# tophat.net
KiCad netlist of a schematic drawn in EAGLE
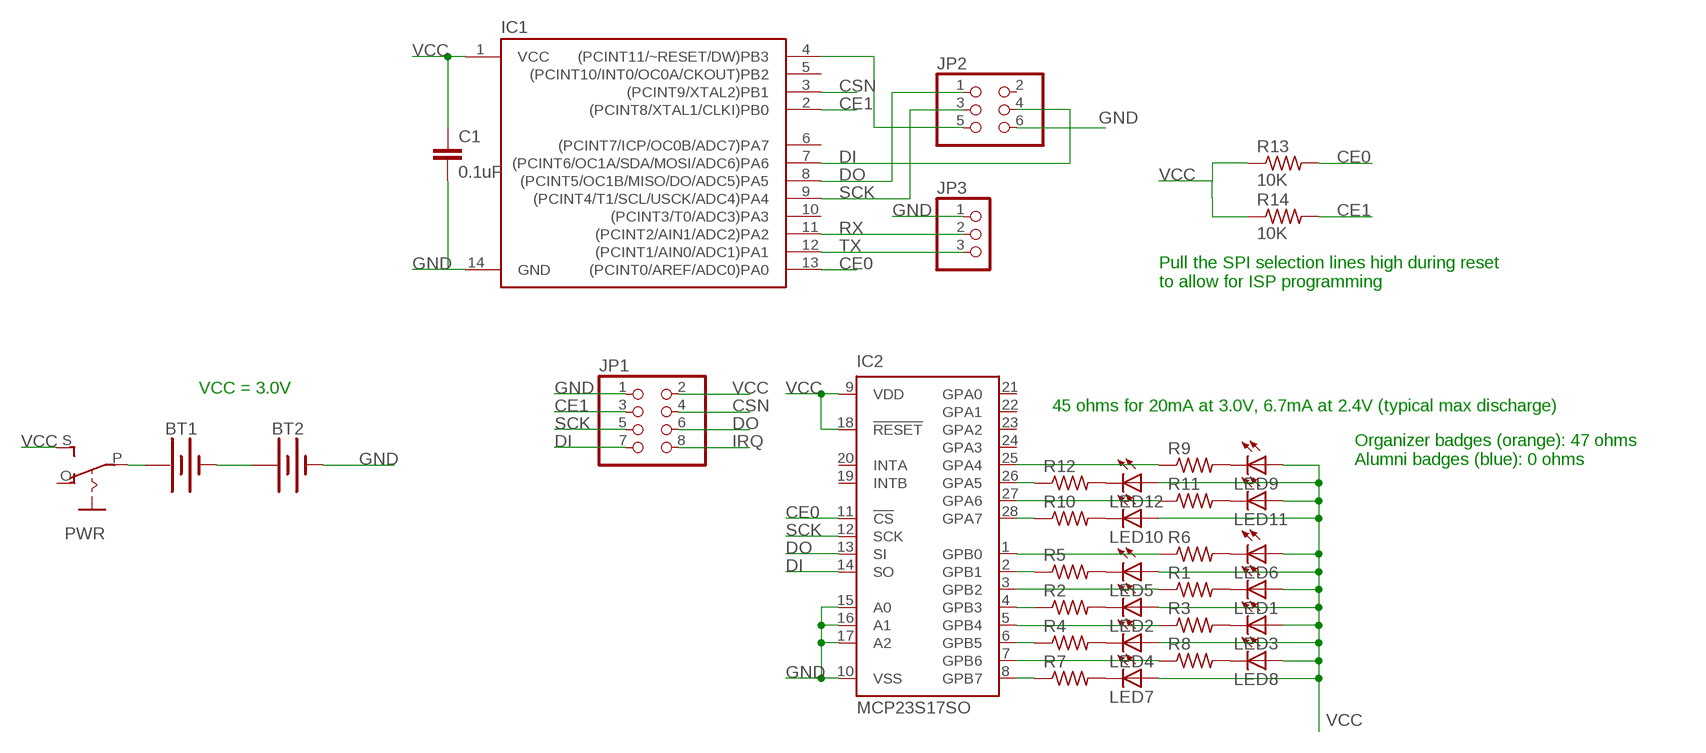
[diagram p0: schematic, sheet 1]

(export (version "E")
  (design (tool "Eeschema 10.0.6"))
  (components
    (comp (ref "BT1")
      (value "BATTERY-AA-SMD")
      (footprint "eagle-import:BATTERY-AA-SMD")
      (libsource (lib "eagle-import") (part "BATTERY-AA-SMD"))
    )
    (comp (ref "BT2")
      (value "BATTERY-AA-SMD")
      (footprint "eagle-import:BATTERY-AA-SMD")
      (libsource (lib "eagle-import") (part "BATTERY-AA-SMD"))
    )
    (comp (ref "C1")
      (value "0.1uF")
      (footprint "eagle-import:C1206")
      (libsource (lib "eagle-import") (part "C-EUC1206"))
    )
    (comp (ref "IC1")
      (value "ATTINY84")
      (footprint "eagle-import:SO14")
      (libsource (lib "eagle-import") (part "ATTINY84"))
    )
    (comp (ref "IC2")
      (value "MCP23S17SO")
      (footprint "eagle-import:SO28W")
      (fields (field (name "MF") "MICROCHIP") (field (name "MPN") "MCP23S17-E/SO"))
      (libsource (lib "eagle-import") (part "MCP23S17SO"))
    )
    (comp (ref "JP1")
      (value "PINHD-2X4/90")
      (footprint "eagle-import:2X04_90")
      (libsource (lib "eagle-import") (part "PINHD-2X4/90"))
    )
    (comp (ref "JP2")
      (value "PINHD-2X3")
      (footprint "eagle-import:2X03")
      (libsource (lib "eagle-import") (part "PINHD-2X3"))
    )
    (comp (ref "JP3")
      (value "PINHD-1X3")
      (footprint "eagle-import:1X03")
      (libsource (lib "eagle-import") (part "PINHD-1X3"))
    )
    (comp (ref "LED1")
      (value "LEDSMT1206")
      (footprint "eagle-import:1206")
      (libsource (lib "eagle-import") (part "LEDSMT1206"))
    )
    (comp (ref "LED2")
      (value "LEDSMT1206")
      (footprint "eagle-import:1206")
      (libsource (lib "eagle-import") (part "LEDSMT1206"))
    )
    (comp (ref "LED3")
      (value "LEDSMT1206")
      (footprint "eagle-import:1206")
      (libsource (lib "eagle-import") (part "LEDSMT1206"))
    )
    (comp (ref "LED4")
      (value "LEDSMT1206")
      (footprint "eagle-import:1206")
      (libsource (lib "eagle-import") (part "LEDSMT1206"))
    )
    (comp (ref "LED5")
      (value "LEDSMT1206")
      (footprint "eagle-import:1206")
      (libsource (lib "eagle-import") (part "LEDSMT1206"))
    )
    (comp (ref "LED6")
      (value "LEDSMT1206")
      (footprint "eagle-import:1206")
      (libsource (lib "eagle-import") (part "LEDSMT1206"))
    )
    (comp (ref "LED7")
      (value "LEDSMT1206")
      (footprint "eagle-import:1206")
      (libsource (lib "eagle-import") (part "LEDSMT1206"))
    )
    (comp (ref "LED8")
      (value "LEDSMT1206")
      (footprint "eagle-import:1206")
      (libsource (lib "eagle-import") (part "LEDSMT1206"))
    )
    (comp (ref "LED9")
      (value "LEDSMT1206")
      (footprint "eagle-import:1206")
      (libsource (lib "eagle-import") (part "LEDSMT1206"))
    )
    (comp (ref "LED10")
      (value "LEDSMT1206")
      (footprint "eagle-import:1206")
      (libsource (lib "eagle-import") (part "LEDSMT1206"))
    )
    (comp (ref "LED11")
      (value "LEDSMT1206")
      (footprint "eagle-import:1206")
      (libsource (lib "eagle-import") (part "LEDSMT1206"))
    )
    (comp (ref "LED12")
      (value "LEDSMT1206")
      (footprint "eagle-import:1206")
      (libsource (lib "eagle-import") (part "LEDSMT1206"))
    )
    (comp (ref "PWR")
      (value "EG1218S")
      (footprint "eagle-import:EG1218")
      (libsource (lib "eagle-import") (part "EG1218S"))
    )
    (comp (ref "R1")
      (value "R-US_R1206")
      (footprint "eagle-import:R1206")
      (libsource (lib "eagle-import") (part "R-US_R1206"))
    )
    (comp (ref "R2")
      (value "R-US_R1206")
      (footprint "eagle-import:R1206")
      (libsource (lib "eagle-import") (part "R-US_R1206"))
    )
    (comp (ref "R3")
      (value "R-US_R1206")
      (footprint "eagle-import:R1206")
      (libsource (lib "eagle-import") (part "R-US_R1206"))
    )
    (comp (ref "R4")
      (value "R-US_R1206")
      (footprint "eagle-import:R1206")
      (libsource (lib "eagle-import") (part "R-US_R1206"))
    )
    (comp (ref "R5")
      (value "R-US_R1206")
      (footprint "eagle-import:R1206")
      (libsource (lib "eagle-import") (part "R-US_R1206"))
    )
    (comp (ref "R6")
      (value "R-US_R1206")
      (footprint "eagle-import:R1206")
      (libsource (lib "eagle-import") (part "R-US_R1206"))
    )
    (comp (ref "R7")
      (value "R-US_R1206")
      (footprint "eagle-import:R1206")
      (libsource (lib "eagle-import") (part "R-US_R1206"))
    )
    (comp (ref "R8")
      (value "R-US_R1206")
      (footprint "eagle-import:R1206")
      (libsource (lib "eagle-import") (part "R-US_R1206"))
    )
    (comp (ref "R9")
      (value "R-US_R1206")
      (footprint "eagle-import:R1206")
      (libsource (lib "eagle-import") (part "R-US_R1206"))
    )
    (comp (ref "R10")
      (value "R-US_R1206")
      (footprint "eagle-import:R1206")
      (libsource (lib "eagle-import") (part "R-US_R1206"))
    )
    (comp (ref "R11")
      (value "R-US_R1206")
      (footprint "eagle-import:R1206")
      (libsource (lib "eagle-import") (part "R-US_R1206"))
    )
    (comp (ref "R12")
      (value "R-US_R1206")
      (footprint "eagle-import:R1206")
      (libsource (lib "eagle-import") (part "R-US_R1206"))
    )
    (comp (ref "R13")
      (value "10K")
      (footprint "eagle-import:R1206")
      (libsource (lib "eagle-import") (part "R-US_R1206"))
    )
    (comp (ref "R14")
      (value "10K")
      (footprint "eagle-import:R1206")
      (libsource (lib "eagle-import") (part "R-US_R1206"))
    )
  )
  (nets
    (net (code "1") (name "/CE0") (class "Default")
      (node (ref "IC1") (pin "13") (pinfunction "(PCINT0/AREF/ADC0)PA0_13") (pintype "bidirectional"))
      (node (ref "IC2") (pin "11") (pinfunction "~{CS}_11") (pintype "input"))
      (node (ref "R13") (pin "2") (pinfunction "2_2") (pintype "passive"))
    )
    (net (code "2") (name "/CE1") (class "Default")
      (node (ref "IC1") (pin "2") (pinfunction "(PCINT8/XTAL1/CLKI)PB0_2") (pintype "bidirectional"))
      (node (ref "JP1") (pin "3") (pinfunction "3_3") (pintype "passive"))
      (node (ref "R14") (pin "2") (pinfunction "2_2") (pintype "passive"))
    )
    (net (code "3") (name "/CSN") (class "Default")
      (node (ref "IC1") (pin "3") (pinfunction "(PCINT9/XTAL2)PB1_3") (pintype "bidirectional"))
      (node (ref "JP1") (pin "4") (pinfunction "4_4") (pintype "passive"))
    )
    (net (code "4") (name "/DI") (class "Default")
      (node (ref "IC1") (pin "7") (pinfunction "(PCINT6/OC1A/SDA/MOSI/ADC6)PA6_7") (pintype "bidirectional"))
      (node (ref "IC2") (pin "14") (pinfunction "SO_14") (pintype "output"))
      (node (ref "JP1") (pin "7") (pinfunction "7_7") (pintype "passive"))
      (node (ref "JP2") (pin "4") (pinfunction "4_4") (pintype "passive"))
    )
    (net (code "5") (name "/DO") (class "Default")
      (node (ref "IC1") (pin "8") (pinfunction "(PCINT5/OC1B/MISO/DO/ADC5)PA5_8") (pintype "bidirectional"))
      (node (ref "IC2") (pin "13") (pinfunction "SI_13") (pintype "input"))
      (node (ref "JP1") (pin "6") (pinfunction "6_6") (pintype "passive"))
      (node (ref "JP2") (pin "1") (pinfunction "1_1") (pintype "passive"))
    )
    (net (code "6") (name "/GND") (class "Default")
      (node (ref "BT2") (pin "P$2") (pinfunction "-_P$2") (pintype "power_in"))
      (node (ref "BT2") (pin "P$4") (pinfunction "-_P$4") (pintype "power_in"))
      (node (ref "C1") (pin "2") (pinfunction "2_2") (pintype "passive"))
      (node (ref "IC1") (pin "14") (pinfunction "GND_14") (pintype "bidirectional"))
      (node (ref "IC2") (pin "10") (pinfunction "VSS_10") (pintype "power_in"))
      (node (ref "IC2") (pin "15") (pinfunction "A0_15") (pintype "input"))
      (node (ref "IC2") (pin "16") (pinfunction "A1_16") (pintype "input"))
      (node (ref "IC2") (pin "17") (pinfunction "A2_17") (pintype "input"))
      (node (ref "JP1") (pin "1") (pinfunction "1_1") (pintype "passive"))
      (node (ref "JP2") (pin "6") (pinfunction "6_6") (pintype "passive"))
      (node (ref "JP3") (pin "1") (pinfunction "1_1") (pintype "passive"))
    )
    (net (code "7") (name "/IRQ") (class "Default")
      (node (ref "JP1") (pin "8") (pinfunction "8_8") (pintype "passive"))
    )
    (net (code "8") (name "/RX") (class "Default")
      (node (ref "IC1") (pin "11") (pinfunction "(PCINT2/AIN1/ADC2)PA2_11") (pintype "bidirectional"))
      (node (ref "JP3") (pin "2") (pinfunction "2_2") (pintype "passive"))
    )
    (net (code "9") (name "/SCK") (class "Default")
      (node (ref "IC1") (pin "9") (pinfunction "(PCINT4/T1/SCL/USCK/ADC4)PA4_9") (pintype "bidirectional"))
      (node (ref "IC2") (pin "12") (pinfunction "SCK_12") (pintype "input"))
      (node (ref "JP1") (pin "5") (pinfunction "5_5") (pintype "passive"))
      (node (ref "JP2") (pin "3") (pinfunction "3_3") (pintype "passive"))
    )
    (net (code "10") (name "/TX") (class "Default")
      (node (ref "IC1") (pin "12") (pinfunction "(PCINT1/AIN0/ADC1)PA1_12") (pintype "bidirectional"))
      (node (ref "JP3") (pin "3") (pinfunction "3_3") (pintype "passive"))
    )
    (net (code "11") (name "/VCC") (class "Default")
      (node (ref "C1") (pin "1") (pinfunction "1_1") (pintype "passive"))
      (node (ref "IC1") (pin "1") (pinfunction "VCC_1") (pintype "bidirectional"))
      (node (ref "IC2") (pin "18") (pinfunction "~{RESET}_18") (pintype "input"))
      (node (ref "IC2") (pin "9") (pinfunction "VDD_9") (pintype "power_in"))
      (node (ref "JP1") (pin "2") (pinfunction "2_2") (pintype "passive"))
      (node (ref "LED1") (pin "A") (pinfunction "A_A") (pintype "passive"))
      (node (ref "LED10") (pin "A") (pinfunction "A_A") (pintype "passive"))
      (node (ref "LED11") (pin "A") (pinfunction "A_A") (pintype "passive"))
      (node (ref "LED12") (pin "A") (pinfunction "A_A") (pintype "passive"))
      (node (ref "LED2") (pin "A") (pinfunction "A_A") (pintype "passive"))
      (node (ref "LED3") (pin "A") (pinfunction "A_A") (pintype "passive"))
      (node (ref "LED4") (pin "A") (pinfunction "A_A") (pintype "passive"))
      (node (ref "LED5") (pin "A") (pinfunction "A_A") (pintype "passive"))
      (node (ref "LED6") (pin "A") (pinfunction "A_A") (pintype "passive"))
      (node (ref "LED7") (pin "A") (pinfunction "A_A") (pintype "passive"))
      (node (ref "LED8") (pin "A") (pinfunction "A_A") (pintype "passive"))
      (node (ref "LED9") (pin "A") (pinfunction "A_A") (pintype "passive"))
      (node (ref "PWR") (pin "S") (pinfunction "S_S") (pintype "passive"))
      (node (ref "R13") (pin "1") (pinfunction "1_1") (pintype "passive"))
      (node (ref "R14") (pin "1") (pinfunction "1_1") (pintype "passive"))
    )
    (net (code "12") (name "Net-(BT1-+-PadP$1)") (class "Default")
      (node (ref "BT1") (pin "P$1") (pinfunction "+_P$1") (pintype "power_in"))
      (node (ref "BT1") (pin "P$3") (pinfunction "+_P$3") (pintype "power_in"))
      (node (ref "PWR") (pin "P") (pinfunction "P_P") (pintype "passive"))
    )
    (net (code "13") (name "Net-(BT1---PadP$2)") (class "Default")
      (node (ref "BT1") (pin "P$2") (pinfunction "-_P$2") (pintype "power_in"))
      (node (ref "BT1") (pin "P$4") (pinfunction "-_P$4") (pintype "power_in"))
      (node (ref "BT2") (pin "P$1") (pinfunction "+_P$1") (pintype "power_in"))
      (node (ref "BT2") (pin "P$3") (pinfunction "+_P$3") (pintype "power_in"))
    )
    (net (code "14") (name "Net-(IC1-(PCINT11{slash}~{RESET{slash}DW})PB3)") (class "Default")
      (node (ref "IC1") (pin "4") (pinfunction "(PCINT11/~{RESET/DW})PB3_4") (pintype "bidirectional"))
      (node (ref "JP2") (pin "5") (pinfunction "5_5") (pintype "passive"))
    )
    (net (code "15") (name "Net-(IC2-GPA4)") (class "Default")
      (node (ref "IC2") (pin "25") (pinfunction "GPA4_25") (pintype "bidirectional"))
      (node (ref "R9") (pin "1") (pinfunction "1_1") (pintype "passive"))
    )
    (net (code "16") (name "Net-(IC2-GPA5)") (class "Default")
      (node (ref "IC2") (pin "26") (pinfunction "GPA5_26") (pintype "bidirectional"))
      (node (ref "R12") (pin "1") (pinfunction "1_1") (pintype "passive"))
    )
    (net (code "17") (name "Net-(IC2-GPA6)") (class "Default")
      (node (ref "IC2") (pin "27") (pinfunction "GPA6_27") (pintype "bidirectional"))
      (node (ref "R11") (pin "1") (pinfunction "1_1") (pintype "passive"))
    )
    (net (code "18") (name "Net-(IC2-GPA7)") (class "Default")
      (node (ref "IC2") (pin "28") (pinfunction "GPA7_28") (pintype "bidirectional"))
      (node (ref "R10") (pin "1") (pinfunction "1_1") (pintype "passive"))
    )
    (net (code "19") (name "Net-(IC2-GPB0)") (class "Default")
      (node (ref "IC2") (pin "1") (pinfunction "GPB0_1") (pintype "bidirectional"))
      (node (ref "R6") (pin "1") (pinfunction "1_1") (pintype "passive"))
    )
    (net (code "20") (name "Net-(IC2-GPB1)") (class "Default")
      (node (ref "IC2") (pin "2") (pinfunction "GPB1_2") (pintype "bidirectional"))
      (node (ref "R5") (pin "1") (pinfunction "1_1") (pintype "passive"))
    )
    (net (code "21") (name "Net-(IC2-GPB2)") (class "Default")
      (node (ref "IC2") (pin "3") (pinfunction "GPB2_3") (pintype "bidirectional"))
      (node (ref "R1") (pin "1") (pinfunction "1_1") (pintype "passive"))
    )
    (net (code "22") (name "Net-(IC2-GPB3)") (class "Default")
      (node (ref "IC2") (pin "4") (pinfunction "GPB3_4") (pintype "bidirectional"))
      (node (ref "R2") (pin "1") (pinfunction "1_1") (pintype "passive"))
    )
    (net (code "23") (name "Net-(IC2-GPB4)") (class "Default")
      (node (ref "IC2") (pin "5") (pinfunction "GPB4_5") (pintype "bidirectional"))
      (node (ref "R3") (pin "1") (pinfunction "1_1") (pintype "passive"))
    )
    (net (code "24") (name "Net-(IC2-GPB5)") (class "Default")
      (node (ref "IC2") (pin "6") (pinfunction "GPB5_6") (pintype "bidirectional"))
      (node (ref "R4") (pin "1") (pinfunction "1_1") (pintype "passive"))
    )
    (net (code "25") (name "Net-(IC2-GPB6)") (class "Default")
      (node (ref "IC2") (pin "7") (pinfunction "GPB6_7") (pintype "bidirectional"))
      (node (ref "R8") (pin "1") (pinfunction "1_1") (pintype "passive"))
    )
    (net (code "26") (name "Net-(IC2-GPB7)") (class "Default")
      (node (ref "IC2") (pin "8") (pinfunction "GPB7_8") (pintype "bidirectional"))
      (node (ref "R7") (pin "1") (pinfunction "1_1") (pintype "passive"))
    )
    (net (code "27") (name "Net-(LED1-PadC)") (class "Default")
      (node (ref "LED1") (pin "C") (pinfunction "C_C") (pintype "passive"))
      (node (ref "R1") (pin "2") (pinfunction "2_2") (pintype "passive"))
    )
    (net (code "28") (name "Net-(LED2-PadC)") (class "Default")
      (node (ref "LED2") (pin "C") (pinfunction "C_C") (pintype "passive"))
      (node (ref "R2") (pin "2") (pinfunction "2_2") (pintype "passive"))
    )
    (net (code "29") (name "Net-(LED3-PadC)") (class "Default")
      (node (ref "LED3") (pin "C") (pinfunction "C_C") (pintype "passive"))
      (node (ref "R3") (pin "2") (pinfunction "2_2") (pintype "passive"))
    )
    (net (code "30") (name "Net-(LED4-PadC)") (class "Default")
      (node (ref "LED4") (pin "C") (pinfunction "C_C") (pintype "passive"))
      (node (ref "R4") (pin "2") (pinfunction "2_2") (pintype "passive"))
    )
    (net (code "31") (name "Net-(LED5-PadC)") (class "Default")
      (node (ref "LED5") (pin "C") (pinfunction "C_C") (pintype "passive"))
      (node (ref "R5") (pin "2") (pinfunction "2_2") (pintype "passive"))
    )
    (net (code "32") (name "Net-(LED6-PadC)") (class "Default")
      (node (ref "LED6") (pin "C") (pinfunction "C_C") (pintype "passive"))
      (node (ref "R6") (pin "2") (pinfunction "2_2") (pintype "passive"))
    )
    (net (code "33") (name "Net-(LED7-PadC)") (class "Default")
      (node (ref "LED7") (pin "C") (pinfunction "C_C") (pintype "passive"))
      (node (ref "R7") (pin "2") (pinfunction "2_2") (pintype "passive"))
    )
    (net (code "34") (name "Net-(LED8-PadC)") (class "Default")
      (node (ref "LED8") (pin "C") (pinfunction "C_C") (pintype "passive"))
      (node (ref "R8") (pin "2") (pinfunction "2_2") (pintype "passive"))
    )
    (net (code "35") (name "Net-(LED9-PadC)") (class "Default")
      (node (ref "LED9") (pin "C") (pinfunction "C_C") (pintype "passive"))
      (node (ref "R9") (pin "2") (pinfunction "2_2") (pintype "passive"))
    )
    (net (code "36") (name "Net-(LED10-PadC)") (class "Default")
      (node (ref "LED10") (pin "C") (pinfunction "C_C") (pintype "passive"))
      (node (ref "R10") (pin "2") (pinfunction "2_2") (pintype "passive"))
    )
    (net (code "37") (name "Net-(LED11-PadC)") (class "Default")
      (node (ref "LED11") (pin "C") (pinfunction "C_C") (pintype "passive"))
      (node (ref "R11") (pin "2") (pinfunction "2_2") (pintype "passive"))
    )
    (net (code "38") (name "Net-(LED12-PadC)") (class "Default")
      (node (ref "LED12") (pin "C") (pinfunction "C_C") (pintype "passive"))
      (node (ref "R12") (pin "2") (pinfunction "2_2") (pintype "passive"))
    )
    (net (code "39") (name "unconnected-(IC1-(PCINT3{slash}T0{slash}ADC3)PA3-Pad10)") (class "Default")
      (node (ref "IC1") (pin "10") (pinfunction "(PCINT3/T0/ADC3)PA3_10") (pintype "bidirectional"))
    )
    (net (code "40") (name "unconnected-(IC1-(PCINT7{slash}ICP{slash}OC0B{slash}ADC7)PA7-Pad6)") (class "Default")
      (node (ref "IC1") (pin "6") (pinfunction "(PCINT7/ICP/OC0B/ADC7)PA7_6") (pintype "bidirectional"))
    )
    (net (code "41") (name "unconnected-(IC1-(PCINT10{slash}INT0{slash}OC0A{slash}CKOUT)PB2-Pad5)") (class "Default")
      (node (ref "IC1") (pin "5") (pinfunction "(PCINT10/INT0/OC0A/CKOUT)PB2_5") (pintype "bidirectional"))
    )
    (net (code "42") (name "unconnected-(IC2-GPA0-Pad21)") (class "Default")
      (node (ref "IC2") (pin "21") (pinfunction "GPA0_21") (pintype "bidirectional"))
    )
    (net (code "43") (name "unconnected-(IC2-GPA1-Pad22)") (class "Default")
      (node (ref "IC2") (pin "22") (pinfunction "GPA1_22") (pintype "bidirectional"))
    )
    (net (code "44") (name "unconnected-(IC2-GPA2-Pad23)") (class "Default")
      (node (ref "IC2") (pin "23") (pinfunction "GPA2_23") (pintype "bidirectional"))
    )
    (net (code "45") (name "unconnected-(IC2-GPA3-Pad24)") (class "Default")
      (node (ref "IC2") (pin "24") (pinfunction "GPA3_24") (pintype "bidirectional"))
    )
    (net (code "46") (name "unconnected-(IC2-INTA-Pad20)") (class "Default")
      (node (ref "IC2") (pin "20") (pinfunction "INTA_20") (pintype "output"))
    )
    (net (code "47") (name "unconnected-(IC2-INTB-Pad19)") (class "Default")
      (node (ref "IC2") (pin "19") (pinfunction "INTB_19") (pintype "output"))
    )
    (net (code "48") (name "unconnected-(JP2-Pad2)") (class "Default")
      (node (ref "JP2") (pin "2") (pinfunction "2_2") (pintype "passive"))
    )
    (net (code "49") (name "unconnected-(PWR-PadO)") (class "Default")
      (node (ref "PWR") (pin "O") (pinfunction "O_O") (pintype "passive"))
    )
  )
)
